# Hardwiring.net
KiCad netlist of a schematic drawn in Altium Designer
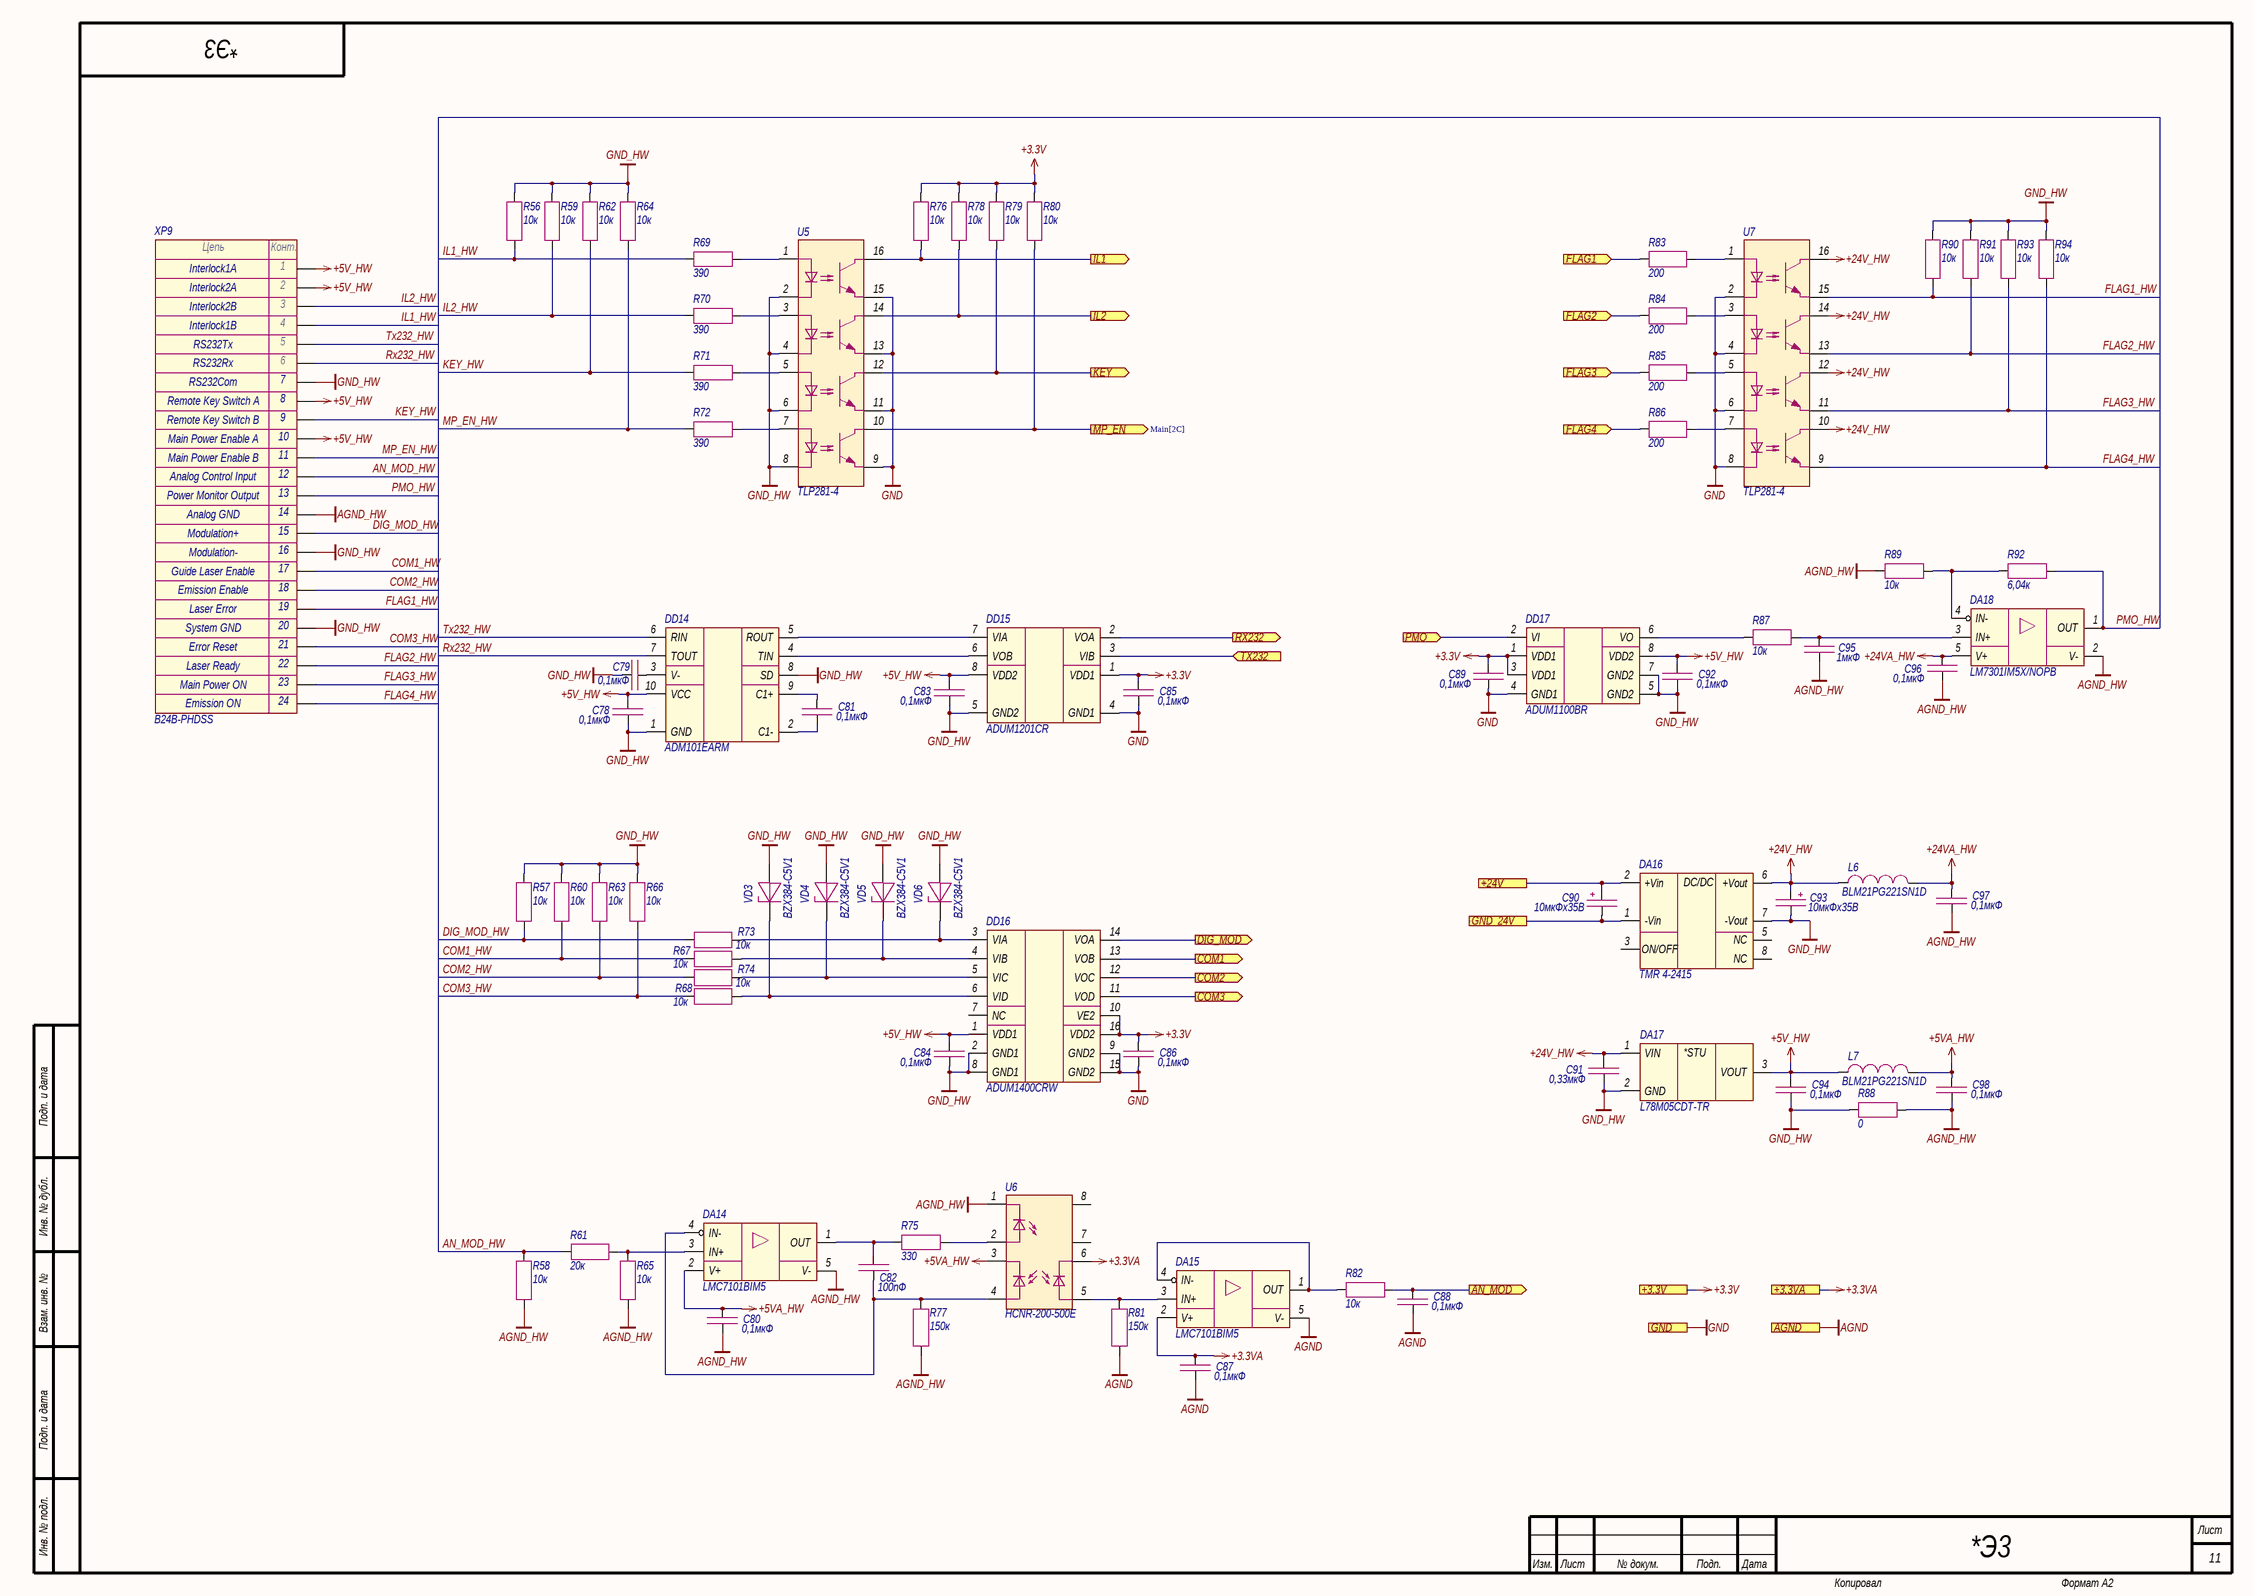
[diagram p0: Hardwiring.SchDoc]

(export (version "E")
  (design (tool "Eeschema 10.0.6"))
  (components
    (comp (ref "C78")
      (value "0,1мкФ")
      (footprint "Pcb_library:CAP_0603")
      (fields (field (name "MANUFACTURER") "Murata"))
      (libsource (lib "Schem_library") (part "Capacitor"))
    )
    (comp (ref "C79")
      (value "0,1мкФ")
      (footprint "Pcb_library:CAP_0603")
      (fields (field (name "MANUFACTURER") "Murata"))
      (libsource (lib "Schem_library") (part "Capacitor"))
    )
    (comp (ref "C80")
      (value "0,1мкФ")
      (footprint "Pcb_library:CAP_0603")
      (fields (field (name "MANUFACTURER") "Murata"))
      (libsource (lib "Schem_library") (part "Capacitor"))
    )
    (comp (ref "C81")
      (value "0,1мкФ")
      (footprint "Pcb_library:CAP_0603")
      (fields (field (name "MANUFACTURER") "Murata"))
      (libsource (lib "Schem_library") (part "Capacitor"))
    )
    (comp (ref "C82")
      (value "100пФ")
      (footprint "Pcb_library:CAP_0603")
      (fields (field (name "MANUFACTURER") "Murata"))
      (libsource (lib "Schem_library") (part "Capacitor"))
    )
    (comp (ref "C83")
      (value "0,1мкФ")
      (footprint "Pcb_library:CAP_0603")
      (fields (field (name "MANUFACTURER") "Murata"))
      (libsource (lib "Schem_library") (part "Capacitor"))
    )
    (comp (ref "C84")
      (value "0,1мкФ")
      (footprint "Pcb_library:CAP_0603")
      (fields (field (name "MANUFACTURER") "Murata"))
      (libsource (lib "Schem_library") (part "Capacitor"))
    )
    (comp (ref "C85")
      (value "0,1мкФ")
      (footprint "Pcb_library:CAP_0603")
      (fields (field (name "MANUFACTURER") "Murata"))
      (libsource (lib "Schem_library") (part "Capacitor"))
    )
    (comp (ref "C86")
      (value "0,1мкФ")
      (footprint "Pcb_library:CAP_0603")
      (fields (field (name "MANUFACTURER") "Murata"))
      (libsource (lib "Schem_library") (part "Capacitor"))
    )
    (comp (ref "C87")
      (value "0,1мкФ")
      (footprint "Pcb_library:CAP_0603")
      (fields (field (name "MANUFACTURER") "Murata"))
      (libsource (lib "Schem_library") (part "Capacitor"))
    )
    (comp (ref "C88")
      (value "0,1мкФ")
      (footprint "Pcb_library:CAP_0603")
      (fields (field (name "MANUFACTURER") "Murata"))
      (libsource (lib "Schem_library") (part "Capacitor"))
    )
    (comp (ref "C89")
      (value "0,1мкФ")
      (footprint "Pcb_library:CAP_0603")
      (fields (field (name "MANUFACTURER") "Murata"))
      (libsource (lib "Schem_library") (part "Capacitor"))
    )
    (comp (ref "C90")
      (value "10мкФх35B")
      (footprint "Pcb_library:CAP_C")
      (libsource (lib "Schem_library") (part "Capacitor_Polar"))
    )
    (comp (ref "C91")
      (value "0,33мкФ")
      (footprint "Pcb_library:CAP_0805")
      (fields (field (name "MANUFACTURER") "Murata"))
      (libsource (lib "Schem_library") (part "Capacitor"))
    )
    (comp (ref "C92")
      (value "0,1мкФ")
      (footprint "Pcb_library:CAP_0603")
      (fields (field (name "MANUFACTURER") "Murata"))
      (libsource (lib "Schem_library") (part "Capacitor"))
    )
    (comp (ref "C93")
      (value "10мкФх35B")
      (footprint "Pcb_library:CAP_C")
      (libsource (lib "Schem_library") (part "Capacitor_Polar"))
    )
    (comp (ref "C94")
      (value "0,1мкФ")
      (footprint "Pcb_library:CAP_0603")
      (fields (field (name "MANUFACTURER") "Murata"))
      (libsource (lib "Schem_library") (part "Capacitor"))
    )
    (comp (ref "C95")
      (value "1мкФ")
      (footprint "Pcb_library:CAP_0603")
      (fields (field (name "MANUFACTURER") "Murata"))
      (libsource (lib "Schem_library") (part "Capacitor"))
    )
    (comp (ref "C96")
      (value "0,1мкФ")
      (footprint "Pcb_library:CAP_0603")
      (fields (field (name "MANUFACTURER") "Murata"))
      (libsource (lib "Schem_library") (part "Capacitor"))
    )
    (comp (ref "C97")
      (value "0,1мкФ")
      (footprint "Pcb_library:CAP_0603")
      (fields (field (name "MANUFACTURER") "Murata"))
      (libsource (lib "Schem_library") (part "Capacitor"))
    )
    (comp (ref "C98")
      (value "0,1мкФ")
      (footprint "Pcb_library:CAP_0603")
      (fields (field (name "MANUFACTURER") "Murata"))
      (libsource (lib "Schem_library") (part "Capacitor"))
    )
    (comp (ref "DA14")
      (value "LMC7101BIM5")
      (footprint "Pcb_library:SOT-23-5")
      (fields (field (name "MANUFACTURER") "Texas Instruments"))
      (libsource (lib "Schem_library") (part "LMC7101"))
    )
    (comp (ref "DA15")
      (value "LMC7101BIM5")
      (footprint "Pcb_library:SOT-23-5")
      (fields (field (name "MANUFACTURER") "Texas Instruments"))
      (libsource (lib "Schem_library") (part "LMC7101"))
    )
    (comp (ref "DA16")
      (value "TMR 4-2415")
      (footprint "Pcb_library:TMR4 (SIP-8)")
      (fields (field (name "MANUFACTURER") "Traco Power"))
      (libsource (lib "Schem_library") (part "TMR4"))
    )
    (comp (ref "DA17")
      (value "L78M05CDT-TR")
      (footprint "Pcb_library:TO-252")
      (fields (field (name "MANUFACTURER") "STMicroelectronics"))
      (libsource (lib "Schem_library") (part "L78M"))
    )
    (comp (ref "DA18")
      (value "LM7301IM5X/NOPB")
      (footprint "Pcb_library:SOT-23-5")
      (fields (field (name "MANUFACTURER") "Texas Instruments"))
      (libsource (lib "Schem_library") (part "LM7301IM5"))
    )
    (comp (ref "DD14")
      (value "ADM101EARM")
      (footprint "Pcb_library:MSOP-10")
      (fields (field (name "MANUFACTURER") "Analog Devices"))
      (libsource (lib "Schem_library") (part "ADM101EARM"))
    )
    (comp (ref "DD15")
      (value "ADUM1201CR")
      (footprint "Pcb_library:SOIC-8")
      (fields (field (name "MANUFACTURER") "Analog Devices"))
      (libsource (lib "Schem_library") (part "ADUM1201"))
    )
    (comp (ref "DD16")
      (value "ADUM1400CRW")
      (footprint "Pcb_library:SOIC-16W")
      (fields (field (name "MANUFACTURER") "Analog Devices"))
      (libsource (lib "Schem_library") (part "ADUM1400"))
    )
    (comp (ref "DD17")
      (value "ADUM1100BR")
      (footprint "Pcb_library:SOIC-8")
      (fields (field (name "MANUFACTURER") "Analog Devices"))
      (libsource (lib "Schem_library") (part "ADUM1100"))
    )
    (comp (ref "L6")
      (value "BLM21PG221SN1D")
      (footprint "Pcb_library:IND_0805")
      (fields (field (name "MANUFACTURER") "Murata"))
      (libsource (lib "Schem_library") (part "Inductor"))
    )
    (comp (ref "L7")
      (value "BLM21PG221SN1D")
      (footprint "Pcb_library:IND_0805")
      (fields (field (name "MANUFACTURER") "Murata"))
      (libsource (lib "Schem_library") (part "Inductor"))
    )
    (comp (ref "R56")
      (value "10к")
      (footprint "Pcb_library:RES_0603")
      (fields (field (name "MANUFACTURER") "Yageo"))
      (libsource (lib "Schem_library") (part "Resistor"))
    )
    (comp (ref "R57")
      (value "10к")
      (footprint "Pcb_library:RES_0603")
      (fields (field (name "MANUFACTURER") "Yageo"))
      (libsource (lib "Schem_library") (part "Resistor"))
    )
    (comp (ref "R58")
      (value "10к")
      (footprint "Pcb_library:RES_0603")
      (fields (field (name "MANUFACTURER") "Yageo"))
      (libsource (lib "Schem_library") (part "Resistor"))
    )
    (comp (ref "R59")
      (value "10к")
      (footprint "Pcb_library:RES_0603")
      (fields (field (name "MANUFACTURER") "Yageo"))
      (libsource (lib "Schem_library") (part "Resistor"))
    )
    (comp (ref "R60")
      (value "10к")
      (footprint "Pcb_library:RES_0603")
      (fields (field (name "MANUFACTURER") "Yageo"))
      (libsource (lib "Schem_library") (part "Resistor"))
    )
    (comp (ref "R61")
      (value "20к")
      (footprint "Pcb_library:RES_0603")
      (fields (field (name "MANUFACTURER") "Yageo"))
      (libsource (lib "Schem_library") (part "Resistor"))
    )
    (comp (ref "R62")
      (value "10к")
      (footprint "Pcb_library:RES_0603")
      (fields (field (name "MANUFACTURER") "Yageo"))
      (libsource (lib "Schem_library") (part "Resistor"))
    )
    (comp (ref "R63")
      (value "10к")
      (footprint "Pcb_library:RES_0603")
      (fields (field (name "MANUFACTURER") "Yageo"))
      (libsource (lib "Schem_library") (part "Resistor"))
    )
    (comp (ref "R64")
      (value "10к")
      (footprint "Pcb_library:RES_0603")
      (fields (field (name "MANUFACTURER") "Yageo"))
      (libsource (lib "Schem_library") (part "Resistor"))
    )
    (comp (ref "R65")
      (value "10к")
      (footprint "Pcb_library:RES_0603")
      (fields (field (name "MANUFACTURER") "Yageo"))
      (libsource (lib "Schem_library") (part "Resistor"))
    )
    (comp (ref "R66")
      (value "10к")
      (footprint "Pcb_library:RES_0603")
      (fields (field (name "MANUFACTURER") "Yageo"))
      (libsource (lib "Schem_library") (part "Resistor"))
    )
    (comp (ref "R67")
      (value "10к")
      (footprint "Pcb_library:RES_0603")
      (fields (field (name "MANUFACTURER") "Yageo"))
      (libsource (lib "Schem_library") (part "Resistor"))
    )
    (comp (ref "R68")
      (value "10к")
      (footprint "Pcb_library:RES_0603")
      (fields (field (name "MANUFACTURER") "Yageo"))
      (libsource (lib "Schem_library") (part "Resistor"))
    )
    (comp (ref "R69")
      (value "390")
      (footprint "Pcb_library:RES_0603")
      (fields (field (name "MANUFACTURER") "Yageo"))
      (libsource (lib "Schem_library") (part "Resistor"))
    )
    (comp (ref "R70")
      (value "390")
      (footprint "Pcb_library:RES_0603")
      (fields (field (name "MANUFACTURER") "Yageo"))
      (libsource (lib "Schem_library") (part "Resistor"))
    )
    (comp (ref "R71")
      (value "390")
      (footprint "Pcb_library:RES_0603")
      (fields (field (name "MANUFACTURER") "Yageo"))
      (libsource (lib "Schem_library") (part "Resistor"))
    )
    (comp (ref "R72")
      (value "390")
      (footprint "Pcb_library:RES_0603")
      (fields (field (name "MANUFACTURER") "Yageo"))
      (libsource (lib "Schem_library") (part "Resistor"))
    )
    (comp (ref "R73")
      (value "10к")
      (footprint "Pcb_library:RES_0603")
      (fields (field (name "MANUFACTURER") "Yageo"))
      (libsource (lib "Schem_library") (part "Resistor"))
    )
    (comp (ref "R74")
      (value "10к")
      (footprint "Pcb_library:RES_0603")
      (fields (field (name "MANUFACTURER") "Yageo"))
      (libsource (lib "Schem_library") (part "Resistor"))
    )
    (comp (ref "R75")
      (value "330")
      (footprint "Pcb_library:RES_0603")
      (fields (field (name "MANUFACTURER") "Yageo"))
      (libsource (lib "Schem_library") (part "Resistor"))
    )
    (comp (ref "R76")
      (value "10к")
      (footprint "Pcb_library:RES_0603")
      (fields (field (name "MANUFACTURER") "Yageo"))
      (libsource (lib "Schem_library") (part "Resistor"))
    )
    (comp (ref "R77")
      (value "150к")
      (footprint "Pcb_library:RES_0603")
      (fields (field (name "MANUFACTURER") "Yageo"))
      (libsource (lib "Schem_library") (part "Resistor"))
    )
    (comp (ref "R78")
      (value "10к")
      (footprint "Pcb_library:RES_0603")
      (fields (field (name "MANUFACTURER") "Yageo"))
      (libsource (lib "Schem_library") (part "Resistor"))
    )
    (comp (ref "R79")
      (value "10к")
      (footprint "Pcb_library:RES_0603")
      (fields (field (name "MANUFACTURER") "Yageo"))
      (libsource (lib "Schem_library") (part "Resistor"))
    )
    (comp (ref "R80")
      (value "10к")
      (footprint "Pcb_library:RES_0603")
      (fields (field (name "MANUFACTURER") "Yageo"))
      (libsource (lib "Schem_library") (part "Resistor"))
    )
    (comp (ref "R81")
      (value "150к")
      (footprint "Pcb_library:RES_0603")
      (fields (field (name "MANUFACTURER") "Yageo"))
      (libsource (lib "Schem_library") (part "Resistor"))
    )
    (comp (ref "R82")
      (value "10к")
      (footprint "Pcb_library:RES_0603")
      (fields (field (name "MANUFACTURER") "Yageo"))
      (libsource (lib "Schem_library") (part "Resistor"))
    )
    (comp (ref "R83")
      (value "200")
      (footprint "Pcb_library:RES_0603")
      (fields (field (name "MANUFACTURER") "Yageo"))
      (libsource (lib "Schem_library") (part "Resistor"))
    )
    (comp (ref "R84")
      (value "200")
      (footprint "Pcb_library:RES_0603")
      (fields (field (name "MANUFACTURER") "Yageo"))
      (libsource (lib "Schem_library") (part "Resistor"))
    )
    (comp (ref "R85")
      (value "200")
      (footprint "Pcb_library:RES_0603")
      (fields (field (name "MANUFACTURER") "Yageo"))
      (libsource (lib "Schem_library") (part "Resistor"))
    )
    (comp (ref "R86")
      (value "200")
      (footprint "Pcb_library:RES_0603")
      (fields (field (name "MANUFACTURER") "Yageo"))
      (libsource (lib "Schem_library") (part "Resistor"))
    )
    (comp (ref "R87")
      (value "10к")
      (footprint "Pcb_library:RES_0603")
      (fields (field (name "MANUFACTURER") "Yageo"))
      (libsource (lib "Schem_library") (part "Resistor"))
    )
    (comp (ref "R88")
      (value "0")
      (footprint "Pcb_library:RES_0805")
      (fields (field (name "MANUFACTURER") "Yageo"))
      (libsource (lib "Schem_library") (part "Resistor"))
    )
    (comp (ref "R89")
      (value "10к")
      (footprint "Pcb_library:RES_0603")
      (fields (field (name "MANUFACTURER") "Yageo"))
      (libsource (lib "Schem_library") (part "Resistor"))
    )
    (comp (ref "R90")
      (value "10к")
      (footprint "Pcb_library:RES_0603")
      (fields (field (name "MANUFACTURER") "Yageo"))
      (libsource (lib "Schem_library") (part "Resistor"))
    )
    (comp (ref "R91")
      (value "10к")
      (footprint "Pcb_library:RES_0603")
      (fields (field (name "MANUFACTURER") "Yageo"))
      (libsource (lib "Schem_library") (part "Resistor"))
    )
    (comp (ref "R92")
      (value "6,04к")
      (footprint "Pcb_library:RES_0603")
      (fields (field (name "MANUFACTURER") "Yageo"))
      (libsource (lib "Schem_library") (part "Resistor"))
    )
    (comp (ref "R93")
      (value "10к")
      (footprint "Pcb_library:RES_0603")
      (fields (field (name "MANUFACTURER") "Yageo"))
      (libsource (lib "Schem_library") (part "Resistor"))
    )
    (comp (ref "R94")
      (value "10к")
      (footprint "Pcb_library:RES_0603")
      (fields (field (name "MANUFACTURER") "Yageo"))
      (libsource (lib "Schem_library") (part "Resistor"))
    )
    (comp (ref "U5")
      (value "TLP281-4")
      (footprint "Pcb_library:SOP-16")
      (fields (field (name "MANUFACTURER") "Toshiba"))
      (libsource (lib "Schem_library") (part "TLP281-4"))
    )
    (comp (ref "U6")
      (value "HCNR-200-500E")
      (footprint "Pcb_library:HCNR200")
      (fields (field (name "MANUFACTURER") "Avago"))
      (libsource (lib "Schem_library") (part "HCNR200"))
    )
    (comp (ref "U7")
      (value "TLP281-4")
      (footprint "Pcb_library:SOP-16")
      (fields (field (name "MANUFACTURER") "Toshiba"))
      (libsource (lib "Schem_library") (part "TLP281-4"))
    )
    (comp (ref "VD3")
      (value "BZX384-C5V1")
      (footprint "Pcb_library:SOD-323")
      (fields (field (name "MANUFACTURER") "Nexperia"))
      (libsource (lib "Schem_library") (part "Diode_Zener"))
    )
    (comp (ref "VD4")
      (value "BZX384-C5V1")
      (footprint "Pcb_library:SOD-323")
      (fields (field (name "MANUFACTURER") "Nexperia"))
      (libsource (lib "Schem_library") (part "Diode_Zener"))
    )
    (comp (ref "VD5")
      (value "BZX384-C5V1")
      (footprint "Pcb_library:SOD-323")
      (fields (field (name "MANUFACTURER") "Nexperia"))
      (libsource (lib "Schem_library") (part "Diode_Zener"))
    )
    (comp (ref "VD6")
      (value "BZX384-C5V1")
      (footprint "Pcb_library:SOD-323")
      (fields (field (name "MANUFACTURER") "Nexperia"))
      (libsource (lib "Schem_library") (part "Diode_Zener"))
    )
    (comp (ref "XP9")
      (value "B24B-PHDSS")
      (footprint "Pcb_library:B24B-PHDSS")
      (fields (field (name "MANUFACTURER") "JST"))
      (libsource (lib "Schem_library") (part "Connector-24"))
    )
  )
  (nets
    (net (code "1") (name "+3.3V") (class "Default")
      (node (ref "C85") (pin "1") (pinfunction "1_1") (pintype "passive"))
      (node (ref "C86") (pin "1") (pinfunction "1_1") (pintype "passive"))
      (node (ref "C89") (pin "1") (pinfunction "1_1") (pintype "passive"))
      (node (ref "DD15") (pin "1") (pinfunction "VDD1_1") (pintype "passive"))
      (node (ref "DD16") (pin "10") (pinfunction "VE2_10") (pintype "passive"))
      (node (ref "DD16") (pin "16") (pinfunction "VDD2_16") (pintype "passive"))
      (node (ref "DD17") (pin "1") (pinfunction "VDD1_1") (pintype "passive"))
      (node (ref "DD17") (pin "3") (pinfunction "VDD1_3") (pintype "passive"))
      (node (ref "R76") (pin "1") (pinfunction "1_1") (pintype "passive"))
      (node (ref "R78") (pin "1") (pinfunction "1_1") (pintype "passive"))
      (node (ref "R79") (pin "1") (pinfunction "1_1") (pintype "passive"))
      (node (ref "R80") (pin "1") (pinfunction "1_1") (pintype "passive"))
    )
    (net (code "2") (name "+3.3VA") (class "Default")
      (node (ref "C87") (pin "1") (pinfunction "1_1") (pintype "passive"))
      (node (ref "DA15") (pin "2") (pinfunction "V+_2") (pintype "passive"))
      (node (ref "U6") (pin "6") (pintype "passive"))
    )
    (net (code "3") (name "+5VA_HW") (class "Default")
      (node (ref "C80") (pin "1") (pinfunction "1_1") (pintype "passive"))
      (node (ref "C98") (pin "1") (pinfunction "1_1") (pintype "passive"))
      (node (ref "DA14") (pin "2") (pinfunction "V+_2") (pintype "passive"))
      (node (ref "L7") (pin "2") (pinfunction "2_2") (pintype "passive"))
      (node (ref "U6") (pin "3") (pintype "passive"))
    )
    (net (code "4") (name "+5V_HW") (class "Default")
      (node (ref "C78") (pin "1") (pinfunction "1_1") (pintype "passive"))
      (node (ref "C83") (pin "1") (pinfunction "1_1") (pintype "passive"))
      (node (ref "C84") (pin "1") (pinfunction "1_1") (pintype "passive"))
      (node (ref "C92") (pin "1") (pinfunction "1_1") (pintype "passive"))
      (node (ref "C94") (pin "1") (pinfunction "1_1") (pintype "passive"))
      (node (ref "DA17") (pin "3") (pinfunction "VOUT_3") (pintype "passive"))
      (node (ref "DD14") (pin "10") (pinfunction "VCC_10") (pintype "passive"))
      (node (ref "DD15") (pin "8") (pinfunction "VDD2_8") (pintype "passive"))
      (node (ref "DD16") (pin "1") (pinfunction "VDD1_1") (pintype "passive"))
      (node (ref "DD17") (pin "8") (pinfunction "VDD2_8") (pintype "passive"))
      (node (ref "L7") (pin "1") (pinfunction "1_1") (pintype "passive"))
      (node (ref "XP9") (pin "1") (pintype "passive"))
      (node (ref "XP9") (pin "10") (pintype "passive"))
      (node (ref "XP9") (pin "2") (pintype "passive"))
      (node (ref "XP9") (pin "8") (pintype "passive"))
    )
    (net (code "5") (name "+24VA_HW") (class "Default")
      (node (ref "C96") (pin "1") (pinfunction "1_1") (pintype "passive"))
      (node (ref "C97") (pin "1") (pinfunction "1_1") (pintype "passive"))
      (node (ref "DA18") (pin "5") (pinfunction "V+_5") (pintype "passive"))
      (node (ref "L6") (pin "2") (pinfunction "2_2") (pintype "passive"))
    )
    (net (code "6") (name "+24V_HW") (class "Default")
      (node (ref "C91") (pin "2") (pinfunction "2_2") (pintype "passive"))
      (node (ref "C93") (pin "1") (pinfunction "1_1") (pintype "passive"))
      (node (ref "DA16") (pin "6") (pinfunction "+Vout_6") (pintype "passive"))
      (node (ref "DA17") (pin "1") (pinfunction "VIN_1") (pintype "passive"))
      (node (ref "L6") (pin "1") (pinfunction "1_1") (pintype "passive"))
      (node (ref "U7") (pin "10") (pintype "passive"))
      (node (ref "U7") (pin "12") (pintype "passive"))
      (node (ref "U7") (pin "14") (pintype "passive"))
      (node (ref "U7") (pin "16") (pintype "passive"))
    )
    (net (code "7") (name "/+24V") (class "Default")
      (node (ref "C90") (pin "1") (pinfunction "1_1") (pintype "passive"))
      (node (ref "DA16") (pin "2") (pinfunction "+Vin_2") (pintype "passive"))
    )
    (net (code "8") (name "/AN_MOD") (class "Default")
      (node (ref "C88") (pin "1") (pinfunction "1_1") (pintype "passive"))
      (node (ref "R82") (pin "2") (pinfunction "2_2") (pintype "passive"))
    )
    (net (code "9") (name "/AN_MOD_HW") (class "Default")
      (node (ref "R58") (pin "1") (pinfunction "1_1") (pintype "passive"))
      (node (ref "R61") (pin "1") (pinfunction "1_1") (pintype "passive"))
      (node (ref "XP9") (pin "12") (pintype "passive"))
    )
    (net (code "10") (name "/COM1") (class "Default")
      (node (ref "DD16") (pin "13") (pinfunction "VOB_13") (pintype "passive"))
    )
    (net (code "11") (name "/COM1_HW") (class "Default")
      (node (ref "R60") (pin "2") (pinfunction "2_2") (pintype "passive"))
      (node (ref "R67") (pin "1") (pinfunction "1_1") (pintype "passive"))
      (node (ref "XP9") (pin "17") (pintype "passive"))
    )
    (net (code "12") (name "/COM2") (class "Default")
      (node (ref "DD16") (pin "12") (pinfunction "VOC_12") (pintype "passive"))
    )
    (net (code "13") (name "/COM2_HW") (class "Default")
      (node (ref "R63") (pin "2") (pinfunction "2_2") (pintype "passive"))
      (node (ref "R74") (pin "1") (pinfunction "1_1") (pintype "passive"))
      (node (ref "XP9") (pin "18") (pintype "passive"))
    )
    (net (code "14") (name "/COM3") (class "Default")
      (node (ref "DD16") (pin "11") (pinfunction "VOD_11") (pintype "passive"))
    )
    (net (code "15") (name "/COM3_HW") (class "Default")
      (node (ref "R66") (pin "2") (pinfunction "2_2") (pintype "passive"))
      (node (ref "R68") (pin "1") (pinfunction "1_1") (pintype "passive"))
      (node (ref "XP9") (pin "21") (pintype "passive"))
    )
    (net (code "16") (name "/DIG_MOD") (class "Default")
      (node (ref "DD16") (pin "14") (pinfunction "VOA_14") (pintype "passive"))
    )
    (net (code "17") (name "/DIG_MOD_HW") (class "Default")
      (node (ref "R57") (pin "2") (pinfunction "2_2") (pintype "passive"))
      (node (ref "R73") (pin "1") (pinfunction "1_1") (pintype "passive"))
      (node (ref "XP9") (pin "15") (pintype "passive"))
    )
    (net (code "18") (name "/FLAG1") (class "Default")
      (node (ref "R83") (pin "2") (pinfunction "2_2") (pintype "passive"))
    )
    (net (code "19") (name "/FLAG1_HW") (class "Default")
      (node (ref "R90") (pin "2") (pinfunction "2_2") (pintype "passive"))
      (node (ref "U7") (pin "15") (pintype "passive"))
      (node (ref "XP9") (pin "19") (pintype "passive"))
    )
    (net (code "20") (name "/FLAG2") (class "Default")
      (node (ref "R84") (pin "2") (pinfunction "2_2") (pintype "passive"))
    )
    (net (code "21") (name "/FLAG2_HW") (class "Default")
      (node (ref "R91") (pin "2") (pinfunction "2_2") (pintype "passive"))
      (node (ref "U7") (pin "13") (pintype "passive"))
      (node (ref "XP9") (pin "22") (pintype "passive"))
    )
    (net (code "22") (name "/FLAG3") (class "Default")
      (node (ref "R85") (pin "2") (pinfunction "2_2") (pintype "passive"))
    )
    (net (code "23") (name "/FLAG3_HW") (class "Default")
      (node (ref "R93") (pin "2") (pinfunction "2_2") (pintype "passive"))
      (node (ref "U7") (pin "11") (pintype "passive"))
      (node (ref "XP9") (pin "23") (pintype "passive"))
    )
    (net (code "24") (name "/FLAG4") (class "Default")
      (node (ref "R86") (pin "2") (pinfunction "2_2") (pintype "passive"))
    )
    (net (code "25") (name "/FLAG4_HW") (class "Default")
      (node (ref "R94") (pin "2") (pinfunction "2_2") (pintype "passive"))
      (node (ref "U7") (pin "9") (pintype "passive"))
      (node (ref "XP9") (pin "24") (pintype "passive"))
    )
    (net (code "26") (name "/GND_24V") (class "Default")
      (node (ref "C90") (pin "2") (pinfunction "2_2") (pintype "passive"))
      (node (ref "DA16") (pin "1") (pinfunction "-Vin_1") (pintype "passive"))
    )
    (net (code "27") (name "/IL1") (class "Default")
      (node (ref "R76") (pin "2") (pinfunction "2_2") (pintype "passive"))
      (node (ref "U5") (pin "16") (pintype "passive"))
    )
    (net (code "28") (name "/IL1_HW") (class "Default")
      (node (ref "R56") (pin "2") (pinfunction "2_2") (pintype "passive"))
      (node (ref "R69") (pin "1") (pinfunction "1_1") (pintype "passive"))
      (node (ref "XP9") (pin "4") (pintype "passive"))
    )
    (net (code "29") (name "/IL2") (class "Default")
      (node (ref "R78") (pin "2") (pinfunction "2_2") (pintype "passive"))
      (node (ref "U5") (pin "14") (pintype "passive"))
    )
    (net (code "30") (name "/IL2_HW") (class "Default")
      (node (ref "R59") (pin "2") (pinfunction "2_2") (pintype "passive"))
      (node (ref "R70") (pin "1") (pinfunction "1_1") (pintype "passive"))
      (node (ref "XP9") (pin "3") (pintype "passive"))
    )
    (net (code "31") (name "/KEY") (class "Default")
      (node (ref "R79") (pin "2") (pinfunction "2_2") (pintype "passive"))
      (node (ref "U5") (pin "12") (pintype "passive"))
    )
    (net (code "32") (name "/KEY_HW") (class "Default")
      (node (ref "R62") (pin "2") (pinfunction "2_2") (pintype "passive"))
      (node (ref "R71") (pin "1") (pinfunction "1_1") (pintype "passive"))
      (node (ref "XP9") (pin "9") (pintype "passive"))
    )
    (net (code "33") (name "/MP_EN") (class "Default")
      (node (ref "R80") (pin "2") (pinfunction "2_2") (pintype "passive"))
      (node (ref "U5") (pin "10") (pintype "passive"))
    )
    (net (code "34") (name "/MP_EN_HW") (class "Default")
      (node (ref "R64") (pin "2") (pinfunction "2_2") (pintype "passive"))
      (node (ref "R72") (pin "1") (pinfunction "1_1") (pintype "passive"))
      (node (ref "XP9") (pin "11") (pintype "passive"))
    )
    (net (code "35") (name "/PMO") (class "Default")
      (node (ref "DD17") (pin "2") (pinfunction "VI_2") (pintype "passive"))
    )
    (net (code "36") (name "/PMO_HW") (class "Default")
      (node (ref "DA18") (pin "1") (pinfunction "OUT_1") (pintype "passive"))
      (node (ref "R92") (pin "2") (pinfunction "2_2") (pintype "passive"))
      (node (ref "XP9") (pin "13") (pintype "passive"))
    )
    (net (code "37") (name "/RX232") (class "Default")
      (node (ref "DD15") (pin "2") (pinfunction "VOA_2") (pintype "passive"))
    )
    (net (code "38") (name "/Rx232_HW") (class "Default")
      (node (ref "DD14") (pin "7") (pinfunction "TOUT_7") (pintype "passive"))
      (node (ref "XP9") (pin "6") (pintype "passive"))
    )
    (net (code "39") (name "/TX232") (class "Default")
      (node (ref "DD15") (pin "3") (pinfunction "VIB_3") (pintype "passive"))
    )
    (net (code "40") (name "/Tx232_HW") (class "Default")
      (node (ref "DD14") (pin "6") (pinfunction "RIN_6") (pintype "passive"))
      (node (ref "XP9") (pin "5") (pintype "passive"))
    )
    (net (code "41") (name "AGND") (class "Default")
      (node (ref "C87") (pin "2") (pinfunction "2_2") (pintype "passive"))
      (node (ref "C88") (pin "2") (pinfunction "2_2") (pintype "passive"))
      (node (ref "DA15") (pin "5") (pinfunction "V-_5") (pintype "passive"))
      (node (ref "R81") (pin "2") (pinfunction "2_2") (pintype "passive"))
    )
    (net (code "42") (name "AGND_HW") (class "Default")
      (node (ref "C80") (pin "2") (pinfunction "2_2") (pintype "passive"))
      (node (ref "C95") (pin "2") (pinfunction "2_2") (pintype "passive"))
      (node (ref "C96") (pin "2") (pinfunction "2_2") (pintype "passive"))
      (node (ref "C97") (pin "2") (pinfunction "2_2") (pintype "passive"))
      (node (ref "C98") (pin "2") (pinfunction "2_2") (pintype "passive"))
      (node (ref "DA14") (pin "5") (pinfunction "V-_5") (pintype "passive"))
      (node (ref "DA18") (pin "2") (pinfunction "V-_2") (pintype "passive"))
      (node (ref "R58") (pin "2") (pinfunction "2_2") (pintype "passive"))
      (node (ref "R65") (pin "2") (pinfunction "2_2") (pintype "passive"))
      (node (ref "R77") (pin "2") (pinfunction "2_2") (pintype "passive"))
      (node (ref "R88") (pin "2") (pinfunction "2_2") (pintype "passive"))
      (node (ref "R89") (pin "1") (pinfunction "1_1") (pintype "passive"))
      (node (ref "U6") (pin "1") (pintype "passive"))
      (node (ref "XP9") (pin "14") (pintype "passive"))
    )
    (net (code "43") (name "GND") (class "Default")
      (node (ref "C85") (pin "2") (pinfunction "2_2") (pintype "passive"))
      (node (ref "C86") (pin "2") (pinfunction "2_2") (pintype "passive"))
      (node (ref "C89") (pin "2") (pinfunction "2_2") (pintype "passive"))
      (node (ref "DD15") (pin "4") (pinfunction "GND1_4") (pintype "passive"))
      (node (ref "DD16") (pin "15") (pinfunction "GND2_15") (pintype "passive"))
      (node (ref "DD16") (pin "9") (pinfunction "GND2_9") (pintype "passive"))
      (node (ref "DD17") (pin "4") (pinfunction "GND1_4") (pintype "passive"))
      (node (ref "U5") (pin "11") (pintype "passive"))
      (node (ref "U5") (pin "13") (pintype "passive"))
      (node (ref "U5") (pin "15") (pintype "passive"))
      (node (ref "U5") (pin "9") (pintype "passive"))
      (node (ref "U7") (pin "2") (pintype "passive"))
      (node (ref "U7") (pin "4") (pintype "passive"))
      (node (ref "U7") (pin "6") (pintype "passive"))
      (node (ref "U7") (pin "8") (pintype "passive"))
    )
    (net (code "44") (name "GND_HW") (class "Default")
      (node (ref "C78") (pin "2") (pinfunction "2_2") (pintype "passive"))
      (node (ref "C79") (pin "2") (pinfunction "2_2") (pintype "passive"))
      (node (ref "C83") (pin "2") (pinfunction "2_2") (pintype "passive"))
      (node (ref "C84") (pin "2") (pinfunction "2_2") (pintype "passive"))
      (node (ref "C91") (pin "1") (pinfunction "1_1") (pintype "passive"))
      (node (ref "C92") (pin "2") (pinfunction "2_2") (pintype "passive"))
      (node (ref "C93") (pin "2") (pinfunction "2_2") (pintype "passive"))
      (node (ref "C94") (pin "2") (pinfunction "2_2") (pintype "passive"))
      (node (ref "DA16") (pin "7") (pinfunction "-Vout_7") (pintype "passive"))
      (node (ref "DA17") (pin "2") (pinfunction "GND_2") (pintype "passive"))
      (node (ref "DD14") (pin "1") (pinfunction "GND_1") (pintype "passive"))
      (node (ref "DD14") (pin "8") (pinfunction "SD_8") (pintype "passive"))
      (node (ref "DD15") (pin "5") (pinfunction "GND2_5") (pintype "passive"))
      (node (ref "DD16") (pin "2") (pinfunction "GND1_2") (pintype "passive"))
      (node (ref "DD16") (pin "8") (pinfunction "GND1_8") (pintype "passive"))
      (node (ref "DD17") (pin "5") (pinfunction "GND2_5") (pintype "passive"))
      (node (ref "DD17") (pin "7") (pinfunction "GND2_7") (pintype "passive"))
      (node (ref "R56") (pin "1") (pinfunction "1_1") (pintype "passive"))
      (node (ref "R57") (pin "1") (pinfunction "1_1") (pintype "passive"))
      (node (ref "R59") (pin "1") (pinfunction "1_1") (pintype "passive"))
      (node (ref "R60") (pin "1") (pinfunction "1_1") (pintype "passive"))
      (node (ref "R62") (pin "1") (pinfunction "1_1") (pintype "passive"))
      (node (ref "R63") (pin "1") (pinfunction "1_1") (pintype "passive"))
      (node (ref "R64") (pin "1") (pinfunction "1_1") (pintype "passive"))
      (node (ref "R66") (pin "1") (pinfunction "1_1") (pintype "passive"))
      (node (ref "R88") (pin "1") (pinfunction "1_1") (pintype "passive"))
      (node (ref "R90") (pin "1") (pinfunction "1_1") (pintype "passive"))
      (node (ref "R91") (pin "1") (pinfunction "1_1") (pintype "passive"))
      (node (ref "R93") (pin "1") (pinfunction "1_1") (pintype "passive"))
      (node (ref "R94") (pin "1") (pinfunction "1_1") (pintype "passive"))
      (node (ref "U5") (pin "2") (pintype "passive"))
      (node (ref "U5") (pin "4") (pintype "passive"))
      (node (ref "U5") (pin "6") (pintype "passive"))
      (node (ref "U5") (pin "8") (pintype "passive"))
      (node (ref "VD3") (pin "2") (pinfunction "A_2") (pintype "passive"))
      (node (ref "VD4") (pin "2") (pinfunction "A_2") (pintype "passive"))
      (node (ref "VD5") (pin "2") (pinfunction "A_2") (pintype "passive"))
      (node (ref "VD6") (pin "2") (pinfunction "A_2") (pintype "passive"))
      (node (ref "XP9") (pin "16") (pintype "passive"))
      (node (ref "XP9") (pin "20") (pintype "passive"))
      (node (ref "XP9") (pin "7") (pintype "passive"))
    )
    (net (code "45") (name "Net-(DA14-IN+)") (class "Default")
      (node (ref "DA14") (pin "3") (pinfunction "IN+_3") (pintype "passive"))
      (node (ref "R61") (pin "2") (pinfunction "2_2") (pintype "passive"))
      (node (ref "R65") (pin "1") (pinfunction "1_1") (pintype "passive"))
    )
    (net (code "46") (name "Net-(DA14-IN-)") (class "Default")
      (node (ref "C82") (pin "2") (pinfunction "2_2") (pintype "passive"))
      (node (ref "DA14") (pin "4") (pinfunction "IN-_4") (pintype "passive"))
      (node (ref "R77") (pin "1") (pinfunction "1_1") (pintype "passive"))
      (node (ref "U6") (pin "4") (pintype "passive"))
    )
    (net (code "47") (name "Net-(DA14-OUT)") (class "Default")
      (node (ref "C82") (pin "1") (pinfunction "1_1") (pintype "passive"))
      (node (ref "DA14") (pin "1") (pinfunction "OUT_1") (pintype "passive"))
      (node (ref "R75") (pin "1") (pinfunction "1_1") (pintype "passive"))
    )
    (net (code "48") (name "Net-(DA15-IN+)") (class "Default")
      (node (ref "DA15") (pin "3") (pinfunction "IN+_3") (pintype "passive"))
      (node (ref "R81") (pin "1") (pinfunction "1_1") (pintype "passive"))
      (node (ref "U6") (pin "5") (pintype "passive"))
    )
    (net (code "49") (name "Net-(DA15-IN-)") (class "Default")
      (node (ref "DA15") (pin "1") (pinfunction "OUT_1") (pintype "passive"))
      (node (ref "DA15") (pin "4") (pinfunction "IN-_4") (pintype "passive"))
      (node (ref "R82") (pin "1") (pinfunction "1_1") (pintype "passive"))
    )
    (net (code "50") (name "Net-(DA18-IN+)") (class "Default")
      (node (ref "C95") (pin "1") (pinfunction "1_1") (pintype "passive"))
      (node (ref "DA18") (pin "3") (pinfunction "IN+_3") (pintype "passive"))
      (node (ref "R87") (pin "2") (pinfunction "2_2") (pintype "passive"))
    )
    (net (code "51") (name "Net-(DA18-IN-)") (class "Default")
      (node (ref "DA18") (pin "4") (pinfunction "IN-_4") (pintype "passive"))
      (node (ref "R89") (pin "2") (pinfunction "2_2") (pintype "passive"))
      (node (ref "R92") (pin "1") (pinfunction "1_1") (pintype "passive"))
    )
    (net (code "52") (name "Net-(DD14-C1+)") (class "Default")
      (node (ref "C81") (pin "1") (pinfunction "1_1") (pintype "passive"))
      (node (ref "DD14") (pin "9") (pinfunction "C1+_9") (pintype "passive"))
    )
    (net (code "53") (name "Net-(DD14-C1-)") (class "Default")
      (node (ref "C81") (pin "2") (pinfunction "2_2") (pintype "passive"))
      (node (ref "DD14") (pin "2") (pinfunction "C1-_2") (pintype "passive"))
    )
    (net (code "54") (name "Net-(DD14-ROUT)") (class "Default")
      (node (ref "DD14") (pin "5") (pinfunction "ROUT_5") (pintype "passive"))
      (node (ref "DD15") (pin "7") (pinfunction "VIA_7") (pintype "passive"))
    )
    (net (code "55") (name "Net-(DD14-TIN)") (class "Default")
      (node (ref "DD14") (pin "4") (pinfunction "TIN_4") (pintype "passive"))
      (node (ref "DD15") (pin "6") (pinfunction "VOB_6") (pintype "passive"))
    )
    (net (code "56") (name "Net-(DD14-V-)") (class "Default")
      (node (ref "C79") (pin "1") (pinfunction "1_1") (pintype "passive"))
      (node (ref "DD14") (pin "3") (pinfunction "V-_3") (pintype "passive"))
    )
    (net (code "57") (name "Net-(DD16-VIA)") (class "Default")
      (node (ref "DD16") (pin "3") (pinfunction "VIA_3") (pintype "passive"))
      (node (ref "R73") (pin "2") (pinfunction "2_2") (pintype "passive"))
      (node (ref "VD6") (pin "1") (pinfunction "K_1") (pintype "passive"))
    )
    (net (code "58") (name "Net-(DD16-VIB)") (class "Default")
      (node (ref "DD16") (pin "4") (pinfunction "VIB_4") (pintype "passive"))
      (node (ref "R67") (pin "2") (pinfunction "2_2") (pintype "passive"))
      (node (ref "VD5") (pin "1") (pinfunction "K_1") (pintype "passive"))
    )
    (net (code "59") (name "Net-(DD16-VIC)") (class "Default")
      (node (ref "DD16") (pin "5") (pinfunction "VIC_5") (pintype "passive"))
      (node (ref "R74") (pin "2") (pinfunction "2_2") (pintype "passive"))
      (node (ref "VD4") (pin "1") (pinfunction "K_1") (pintype "passive"))
    )
    (net (code "60") (name "Net-(DD16-VID)") (class "Default")
      (node (ref "DD16") (pin "6") (pinfunction "VID_6") (pintype "passive"))
      (node (ref "R68") (pin "2") (pinfunction "2_2") (pintype "passive"))
      (node (ref "VD3") (pin "1") (pinfunction "K_1") (pintype "passive"))
    )
    (net (code "61") (name "Net-(DD17-VO)") (class "Default")
      (node (ref "DD17") (pin "6") (pinfunction "VO_6") (pintype "passive"))
      (node (ref "R87") (pin "1") (pinfunction "1_1") (pintype "passive"))
    )
    (net (code "62") (name "Net-(R69-Pad2)") (class "Default")
      (node (ref "R69") (pin "2") (pinfunction "2_2") (pintype "passive"))
      (node (ref "U5") (pin "1") (pintype "passive"))
    )
    (net (code "63") (name "Net-(R70-Pad2)") (class "Default")
      (node (ref "R70") (pin "2") (pinfunction "2_2") (pintype "passive"))
      (node (ref "U5") (pin "3") (pintype "passive"))
    )
    (net (code "64") (name "Net-(R71-Pad2)") (class "Default")
      (node (ref "R71") (pin "2") (pinfunction "2_2") (pintype "passive"))
      (node (ref "U5") (pin "5") (pintype "passive"))
    )
    (net (code "65") (name "Net-(R72-Pad2)") (class "Default")
      (node (ref "R72") (pin "2") (pinfunction "2_2") (pintype "passive"))
      (node (ref "U5") (pin "7") (pintype "passive"))
    )
    (net (code "66") (name "Net-(R75-Pad2)") (class "Default")
      (node (ref "R75") (pin "2") (pinfunction "2_2") (pintype "passive"))
      (node (ref "U6") (pin "2") (pintype "passive"))
    )
    (net (code "67") (name "Net-(R83-Pad1)") (class "Default")
      (node (ref "R83") (pin "1") (pinfunction "1_1") (pintype "passive"))
      (node (ref "U7") (pin "1") (pintype "passive"))
    )
    (net (code "68") (name "Net-(R84-Pad1)") (class "Default")
      (node (ref "R84") (pin "1") (pinfunction "1_1") (pintype "passive"))
      (node (ref "U7") (pin "3") (pintype "passive"))
    )
    (net (code "69") (name "Net-(R85-Pad1)") (class "Default")
      (node (ref "R85") (pin "1") (pinfunction "1_1") (pintype "passive"))
      (node (ref "U7") (pin "5") (pintype "passive"))
    )
    (net (code "70") (name "Net-(R86-Pad1)") (class "Default")
      (node (ref "R86") (pin "1") (pinfunction "1_1") (pintype "passive"))
      (node (ref "U7") (pin "7") (pintype "passive"))
    )
    (net (code "71") (name "unconnected-(DA16-NC-Pad5)") (class "Default")
      (node (ref "DA16") (pin "5") (pinfunction "NC_5") (pintype "passive"))
    )
    (net (code "72") (name "unconnected-(DA16-NC-Pad8)") (class "Default")
      (node (ref "DA16") (pin "8") (pinfunction "NC_8") (pintype "passive"))
    )
    (net (code "73") (name "unconnected-(DA16-ON{slash}OFF-Pad3)") (class "Default")
      (node (ref "DA16") (pin "3") (pinfunction "ON/OFF_3") (pintype "passive"))
    )
    (net (code "74") (name "unconnected-(DD16-NC-Pad7)") (class "Default")
      (node (ref "DD16") (pin "7") (pinfunction "NC_7") (pintype "passive"))
    )
    (net (code "75") (name "unconnected-(U6-Pad7)") (class "Default")
      (node (ref "U6") (pin "7") (pintype "passive"))
    )
    (net (code "76") (name "unconnected-(U6-Pad8)") (class "Default")
      (node (ref "U6") (pin "8") (pintype "passive"))
    )
  )
)
